# ProPrj_BAP_PCB_General_Room_2025-11-06.net
KiCad netlist of a schematic drawn in EasyEDA Pro
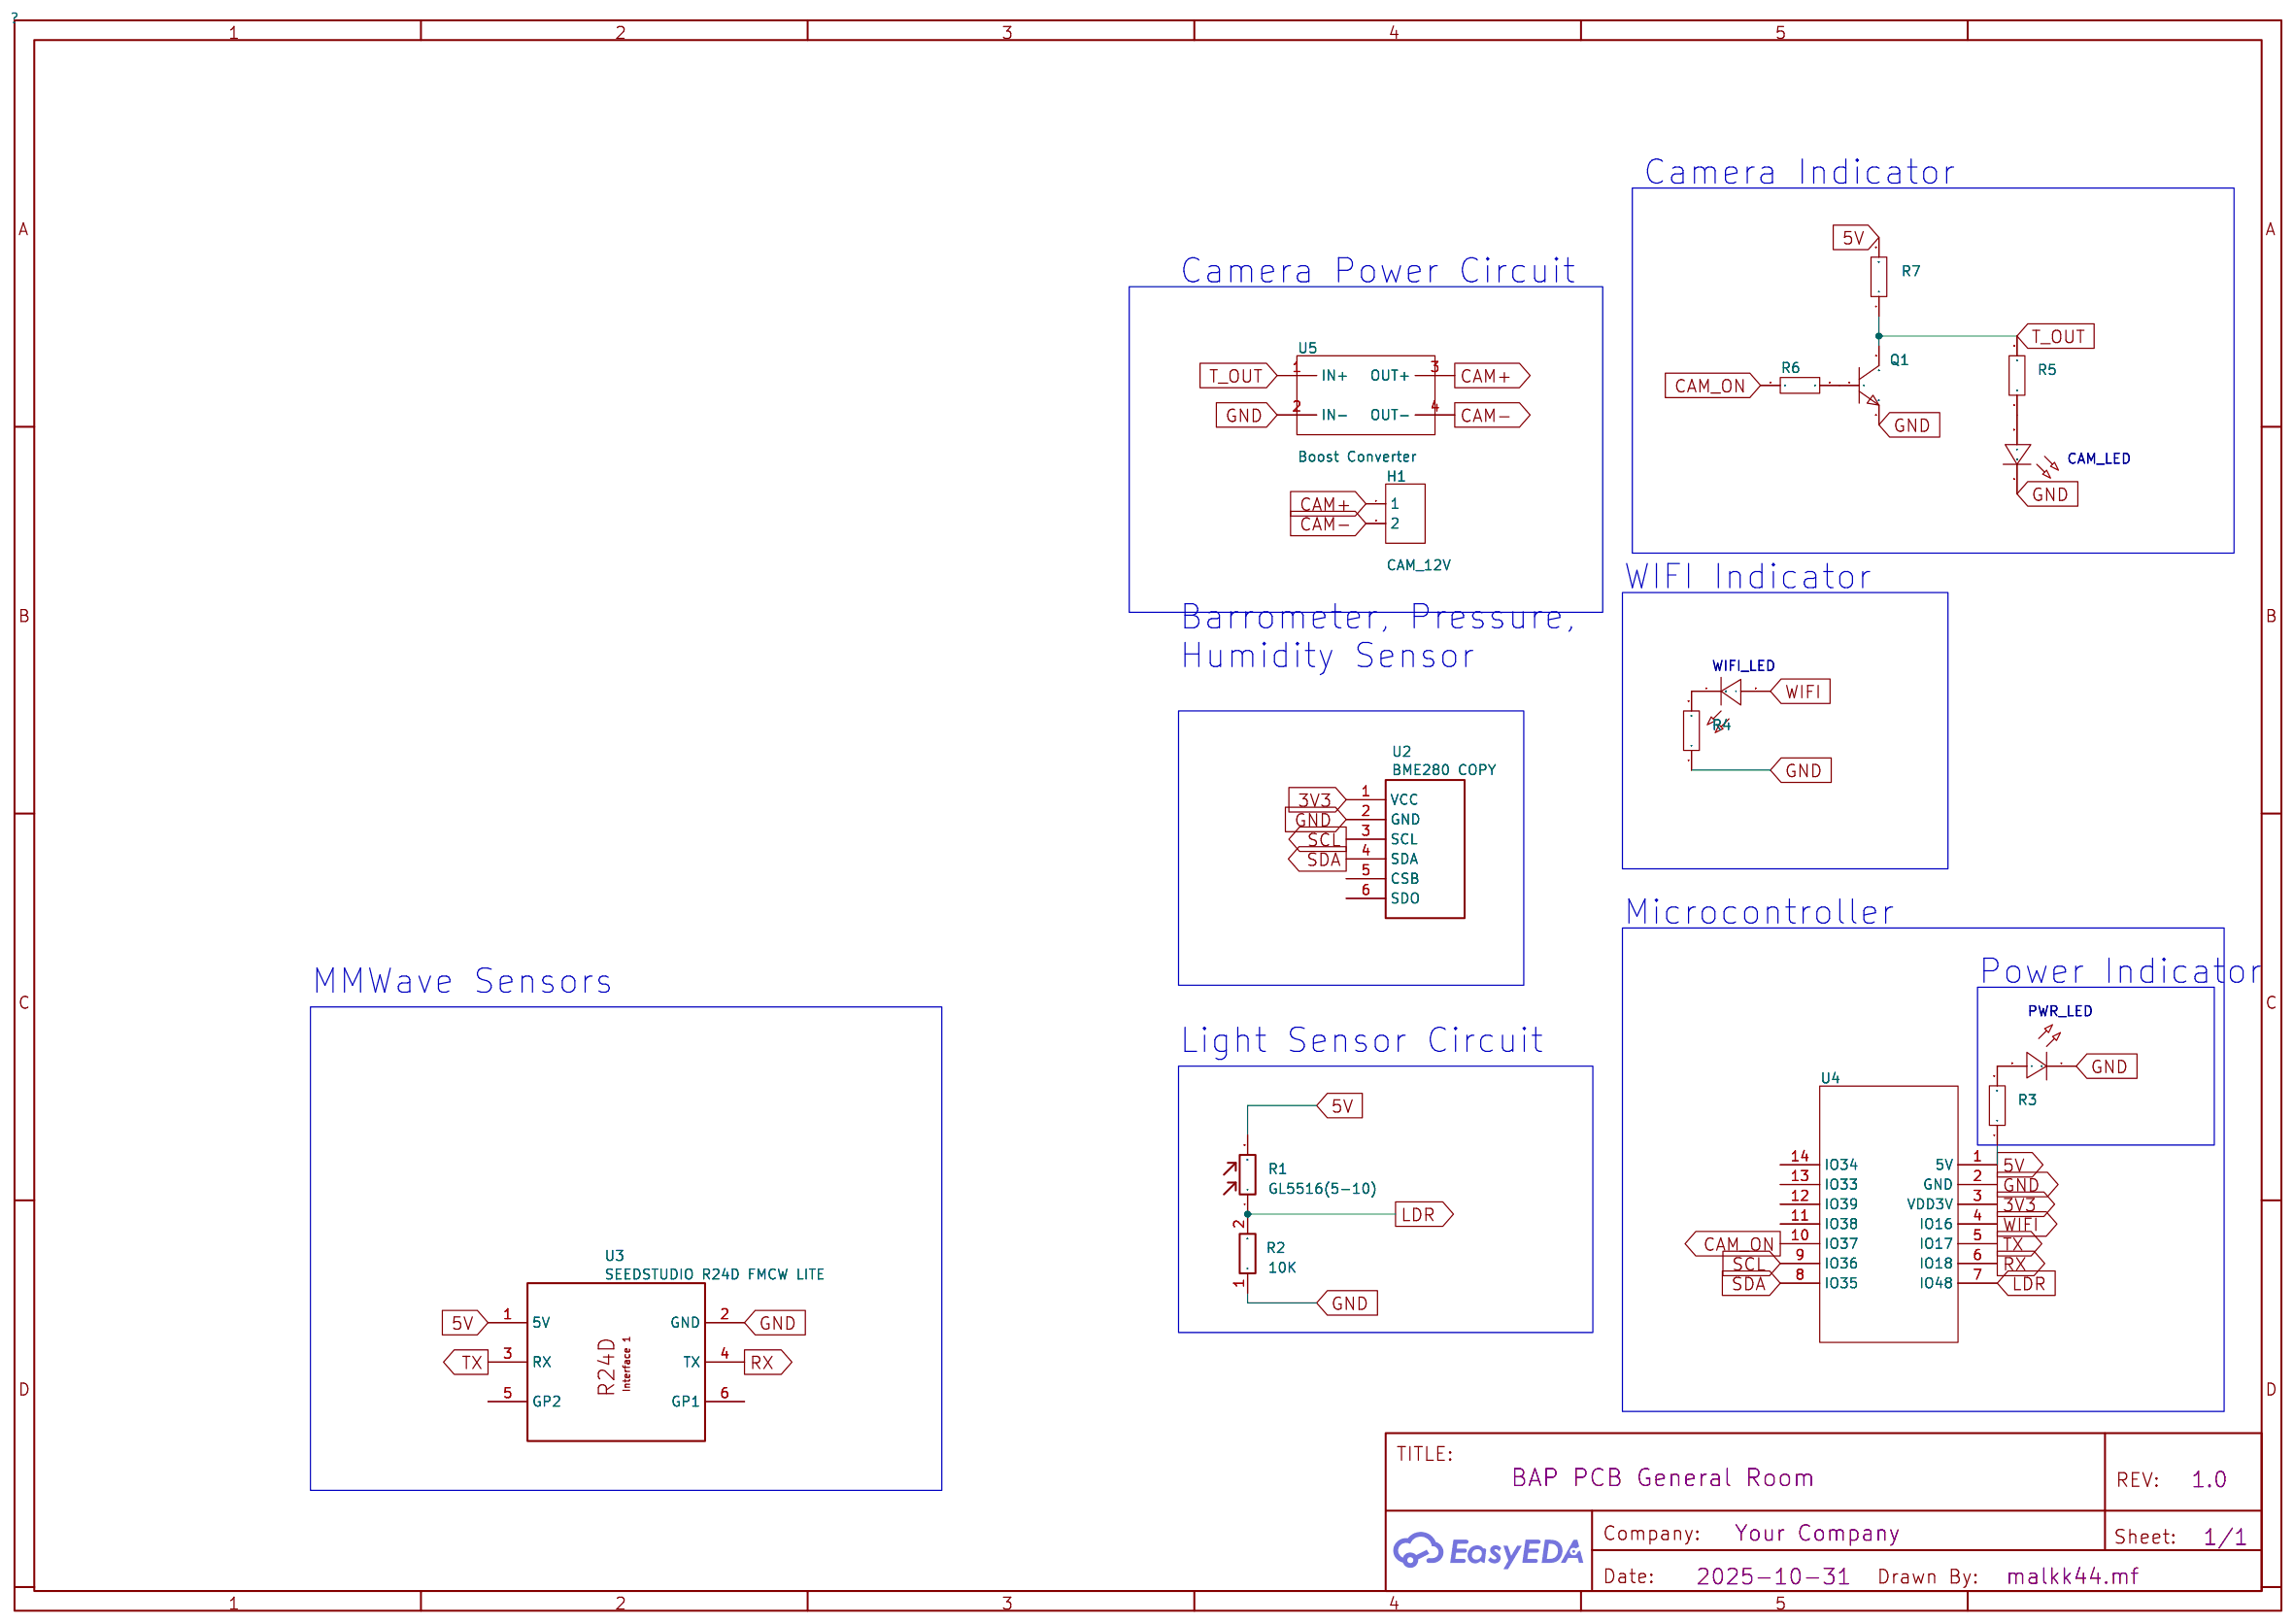
[diagram p0: schematic sheet]

(export (version "E")
  (design (tool "Eeschema 10.0.6"))
  (components
    (comp (ref "CAM_LED")
      (value "~")
      (footprint "easyedapro:LED_0603")
      (libsource (lib "easyedapro") (part "LED_G"))
    )
    (comp (ref "H1")
      (value "CAM_12V")
      (footprint "easyedapro:HDR-TH_2P-P2.54-V-F")
      (libsource (lib "easyedapro") (part "Header-Female-2.54_1x2"))
    )
    (comp (ref "PWR_LED")
      (value "~")
      (footprint "easyedapro:LED_0603")
      (libsource (lib "easyedapro") (part "LED_G"))
    )
    (comp (ref "Q1")
      (value "~")
      (footprint "easyedapro:S8050_SOT-23")
      (libsource (lib "easyedapro") (part "NPN"))
    )
    (comp (ref "R1")
      (value "GL5516(5-10)")
      (fields (field (name "Manufacturer") "JCHL(晶创和立)"))
      (libsource (lib "easyedapro") (part "GL5516(5-10)"))
    )
    (comp (ref "R2")
      (value "10K")
      (fields
        (field (name "Manufacturer Part") "MF1/4W-330Ω±1% T")
        (field (name "Manufacturer") "CCO(千志电子)")
        (field (name "Contributor") "LCSC")
      )
      (libsource (lib "easyedapro") (part "10K"))
    )
    (comp (ref "R3")
      (value "330Ω")
      (footprint "easyedapro:RES-TH_BD2.2-L6.5-P10.50-D0.6")
      (fields (field (name "Manufacturer Part") "MFR-25FTE52-330R") (field (name "Manufacturer") "YAGEO(国巨)"))
      (libsource (lib "easyedapro") (part "MFR-25FTE52-330R"))
    )
    (comp (ref "R4")
      (value "330Ω")
      (footprint "easyedapro:RES-TH_BD2.2-L6.5-P10.50-D0.6")
      (fields (field (name "Manufacturer Part") "MFR-25FTE52-330R") (field (name "Manufacturer") "YAGEO(国巨)"))
      (libsource (lib "easyedapro") (part "MFR-25FTE52-330R"))
    )
    (comp (ref "R5")
      (value "330Ω")
      (footprint "easyedapro:RES-TH_BD2.2-L6.5-P10.50-D0.6")
      (fields (field (name "Manufacturer Part") "MFR-25FTE52-330R") (field (name "Manufacturer") "YAGEO(国巨)"))
      (libsource (lib "easyedapro") (part "MFR-25FTE52-330R"))
    )
    (comp (ref "R6")
      (value "~")
      (footprint "easyedapro:Resistor 1/8w 7mm metal film")
      (fields
        (field (name "Manufacturer Part") "1206W4F1002T5E")
        (field (name "Manufacturer") "UNI-ROYAL(Uniroyal Elec)")
      )
      (libsource (lib "easyedapro") (part "resistor"))
    )
    (comp (ref "R7")
      (value "~")
      (footprint "easyedapro:Resistor 1/8w 7mm metal film")
      (fields
        (field (name "Manufacturer Part") "1206W4F1002T5E")
        (field (name "Manufacturer") "UNI-ROYAL(Uniroyal Elec)")
      )
      (libsource (lib "easyedapro") (part "resistor"))
    )
    (comp (ref "U2")
      (value "BME280 COPY")
      (fields (field (name "Manufacturer Part") "BME280") (field (name "Contributor") "b_amnart"))
      (libsource (lib "easyedapro") (part "BME280 COPY"))
    )
    (comp (ref "U3")
      (value "SEEDSTUDIO R24D FMCW LITE")
      (fields (field (name "Contributor") "hutzomene"))
      (libsource (lib "easyedapro") (part "SEEDSTUDIO R24D FMCW LITE"))
    )
    (comp (ref "U4")
      (value "~")
      (footprint "easyedapro:LilyGO TQ-T Pro")
      (libsource (lib "easyedapro") (part "LilyGO TQ-T Pro"))
    )
    (comp (ref "U5")
      (value "Boost Converter")
      (footprint "easyedapro:Boost Converter")
      (libsource (lib "easyedapro") (part "Boost Converter"))
    )
    (comp (ref "WIFI_LED")
      (value "~")
      (footprint "easyedapro:LED_0603")
      (libsource (lib "easyedapro") (part "LED_G"))
    )
  )
  (nets
    (net (code "1") (name "3V3") (class "Default")
      (node (ref "U2") (pin "1") (pinfunction "VCC_1") (pintype "unspecified"))
      (node (ref "U4") (pin "3") (pinfunction "VDD3V_3") (pintype "output"))
    )
    (net (code "2") (name "5V") (class "Default")
      (node (ref "R1") (pin "2") (pinfunction "2_2") (pintype "input"))
      (node (ref "R3") (pin "1") (pinfunction "1_1") (pintype "input"))
      (node (ref "R7") (pin "2") (pinfunction "2_2") (pintype "input"))
      (node (ref "U3") (pin "1") (pinfunction "5V_1") (pintype "unspecified"))
      (node (ref "U4") (pin "1") (pinfunction "5V_1") (pintype "output"))
    )
    (net (code "3") (name "CAM+") (class "Default")
      (node (ref "H1") (pin "1") (pinfunction "1_1") (pintype "input"))
      (node (ref "U5") (pin "3") (pinfunction "OUT+_3") (pintype "output"))
    )
    (net (code "4") (name "CAM-") (class "Default")
      (node (ref "H1") (pin "2") (pinfunction "2_2") (pintype "input"))
      (node (ref "U5") (pin "4") (pinfunction "OUT-_4") (pintype "output"))
    )
    (net (code "5") (name "CAM_ON") (class "Default")
      (node (ref "R6") (pin "1") (pinfunction "1_1") (pintype "input"))
      (node (ref "U4") (pin "10") (pinfunction "IO37_10") (pintype "bidirectional"))
    )
    (net (code "6") (name "GND") (class "Default")
      (node (ref "CAM_LED") (pin "1") (pinfunction "C_1") (pintype "input"))
      (node (ref "PWR_LED") (pin "1") (pinfunction "C_1") (pintype "input"))
      (node (ref "Q1") (pin "2") (pinfunction "2_2") (pintype "unspecified"))
      (node (ref "R2") (pin "1") (pinfunction "1_1") (pintype "unspecified"))
      (node (ref "R4") (pin "1") (pinfunction "1_1") (pintype "input"))
      (node (ref "U2") (pin "2") (pinfunction "GND_2") (pintype "unspecified"))
      (node (ref "U3") (pin "2") (pinfunction "GND_2") (pintype "unspecified"))
      (node (ref "U4") (pin "2") (pinfunction "GND_2") (pintype "output"))
      (node (ref "U5") (pin "2") (pinfunction "IN-_2") (pintype "input"))
    )
    (net (code "7") (name "LDR") (class "Default")
      (node (ref "R1") (pin "1") (pinfunction "1_1") (pintype "input"))
      (node (ref "R2") (pin "2") (pinfunction "2_2") (pintype "unspecified"))
      (node (ref "U4") (pin "7") (pinfunction "IO48_7") (pintype "bidirectional"))
    )
    (net (code "8") (name "Net-(CAM_LED-A)") (class "Default")
      (node (ref "CAM_LED") (pin "2") (pinfunction "A_2") (pintype "input"))
      (node (ref "R5") (pin "1") (pinfunction "1_1") (pintype "input"))
    )
    (net (code "9") (name "Net-(PWR_LED-A)") (class "Default")
      (node (ref "PWR_LED") (pin "2") (pinfunction "A_2") (pintype "input"))
      (node (ref "R3") (pin "2") (pinfunction "2_2") (pintype "input"))
    )
    (net (code "10") (name "Net-(Q1-Pad1)") (class "Default")
      (node (ref "Q1") (pin "1") (pinfunction "1_1") (pintype "unspecified"))
      (node (ref "R6") (pin "2") (pinfunction "2_2") (pintype "input"))
    )
    (net (code "11") (name "Net-(WIFI_LED-C)") (class "Default")
      (node (ref "R4") (pin "2") (pinfunction "2_2") (pintype "input"))
      (node (ref "WIFI_LED") (pin "1") (pinfunction "C_1") (pintype "input"))
    )
    (net (code "12") (name "RX") (class "Default")
      (node (ref "U3") (pin "4") (pinfunction "TX_4") (pintype "unspecified"))
      (node (ref "U4") (pin "6") (pinfunction "IO18_6") (pintype "bidirectional"))
    )
    (net (code "13") (name "SCL") (class "Default")
      (node (ref "U2") (pin "3") (pinfunction "SCL_3") (pintype "unspecified"))
      (node (ref "U4") (pin "9") (pinfunction "IO36_9") (pintype "bidirectional"))
    )
    (net (code "14") (name "SDA") (class "Default")
      (node (ref "U2") (pin "4") (pinfunction "SDA_4") (pintype "unspecified"))
      (node (ref "U4") (pin "8") (pinfunction "IO35_8") (pintype "bidirectional"))
    )
    (net (code "15") (name "TX") (class "Default")
      (node (ref "U3") (pin "3") (pinfunction "RX_3") (pintype "unspecified"))
      (node (ref "U4") (pin "5") (pinfunction "IO17_5") (pintype "bidirectional"))
    )
    (net (code "16") (name "T_OUT") (class "Default")
      (node (ref "Q1") (pin "3") (pinfunction "3_3") (pintype "unspecified"))
      (node (ref "R5") (pin "2") (pinfunction "2_2") (pintype "input"))
      (node (ref "R7") (pin "1") (pinfunction "1_1") (pintype "input"))
      (node (ref "U5") (pin "1") (pinfunction "IN+_1") (pintype "input"))
    )
    (net (code "17") (name "WIFI") (class "Default")
      (node (ref "U4") (pin "4") (pinfunction "IO16_4") (pintype "bidirectional"))
      (node (ref "WIFI_LED") (pin "2") (pinfunction "A_2") (pintype "input"))
    )
    (net (code "18") (name "unconnected-(U2-CSB-Pad5)") (class "Default")
      (node (ref "U2") (pin "5") (pinfunction "CSB_5") (pintype "unspecified"))
    )
    (net (code "19") (name "unconnected-(U2-SDO-Pad6)") (class "Default")
      (node (ref "U2") (pin "6") (pinfunction "SDO_6") (pintype "unspecified"))
    )
    (net (code "20") (name "unconnected-(U3-GP1-Pad6)") (class "Default")
      (node (ref "U3") (pin "6") (pinfunction "GP1_6") (pintype "unspecified"))
    )
    (net (code "21") (name "unconnected-(U3-GP2-Pad5)") (class "Default")
      (node (ref "U3") (pin "5") (pinfunction "GP2_5") (pintype "unspecified"))
    )
    (net (code "22") (name "unconnected-(U4-IO33-Pad13)") (class "Default")
      (node (ref "U4") (pin "13") (pinfunction "IO33_13") (pintype "bidirectional"))
    )
    (net (code "23") (name "unconnected-(U4-IO34-Pad14)") (class "Default")
      (node (ref "U4") (pin "14") (pinfunction "IO34_14") (pintype "bidirectional"))
    )
    (net (code "24") (name "unconnected-(U4-IO38-Pad11)") (class "Default")
      (node (ref "U4") (pin "11") (pinfunction "IO38_11") (pintype "bidirectional"))
    )
    (net (code "25") (name "unconnected-(U4-IO39-Pad12)") (class "Default")
      (node (ref "U4") (pin "12") (pinfunction "IO39_12") (pintype "bidirectional"))
    )
  )
)
